# UNG_8088_EVB_LAN9252-SPI_Copper.net
KiCad netlist of a schematic drawn in Altium Designer
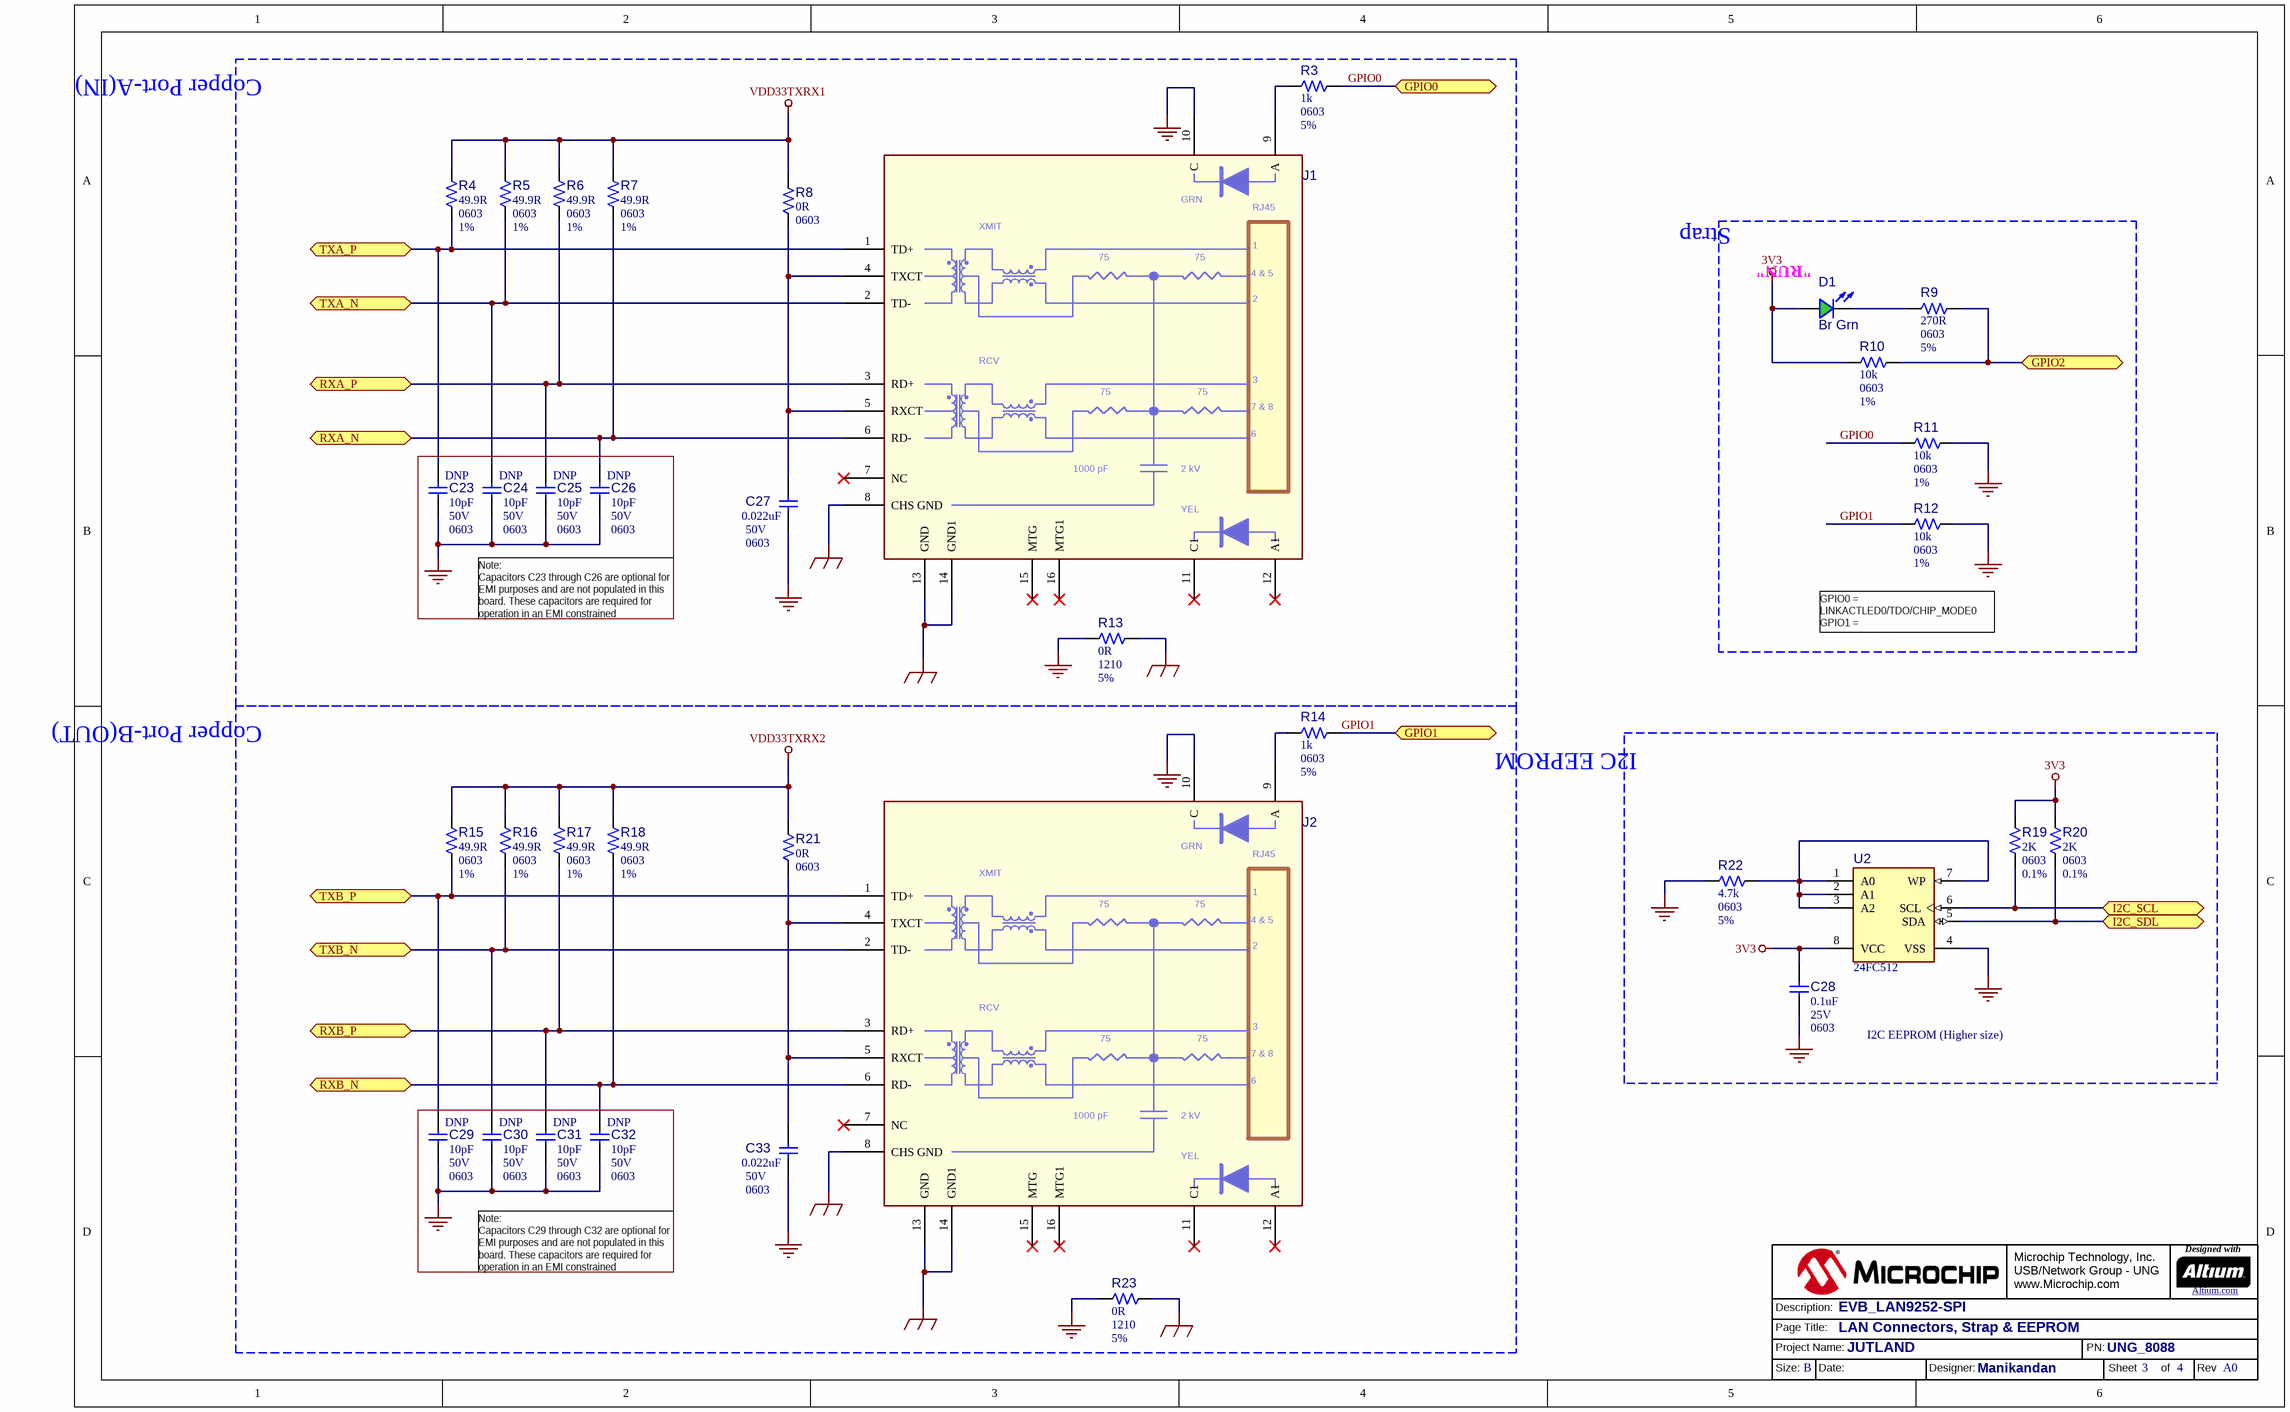
[diagram p0: UNG_8088_EVB_LAN9252-SPI_Copper.SchDoc]

(export (version "E")
  (design (tool "Eeschema 10.0.6"))
  (components
    (comp (ref "C23")
      (value "10pF")
      (footprint "CAP_C_0603")
      (description "Capacitor")
      (fields
        (field (name "VOLTAGE") "50V")
        (field (name "PACKAGE") "0603")
        (field (name "TOLERANCE") "5%")
        (field (name "POPULATED") "DNP")
        (field (name "Comment") "Capacitor NP")
      )
      (libsource (lib "MCHP-CDB-Offline") (part "Capacitor NP"))
    )
    (comp (ref "C24")
      (value "10pF")
      (footprint "CAP_C_0603")
      (description "Capacitor")
      (fields
        (field (name "VOLTAGE") "50V")
        (field (name "PACKAGE") "0603")
        (field (name "TOLERANCE") "5%")
        (field (name "POPULATED") "DNP")
        (field (name "Comment") "Capacitor NP")
      )
      (libsource (lib "MCHP-CDB-Offline") (part "Capacitor NP"))
    )
    (comp (ref "C25")
      (value "10pF")
      (footprint "CAP_C_0603")
      (description "Capacitor")
      (fields
        (field (name "VOLTAGE") "50V")
        (field (name "PACKAGE") "0603")
        (field (name "TOLERANCE") "5%")
        (field (name "POPULATED") "DNP")
        (field (name "Comment") "Capacitor NP")
      )
      (libsource (lib "MCHP-CDB-Offline") (part "Capacitor NP"))
    )
    (comp (ref "C26")
      (value "10pF")
      (footprint "CAP_C_0603")
      (description "Capacitor")
      (fields
        (field (name "VOLTAGE") "50V")
        (field (name "PACKAGE") "0603")
        (field (name "TOLERANCE") "5%")
        (field (name "POPULATED") "DNP")
        (field (name "Comment") "Capacitor NP")
      )
      (libsource (lib "MCHP-CDB-Offline") (part "Capacitor NP"))
    )
    (comp (ref "C27")
      (value "0.022uF")
      (footprint "CAP_C_0603")
      (description "Capacitor")
      (fields
        (field (name "VOLTAGE") "50V")
        (field (name "PACKAGE") "0603")
        (field (name "TOLERANCE") "5%")
        (field (name "Comment") "Capacitor NP")
      )
      (libsource (lib "MCHP-CDB-Offline") (part "Capacitor NP"))
    )
    (comp (ref "C28")
      (value "0.1uF")
      (footprint "CAP_C_0603")
      (description "Capacitor")
      (fields
        (field (name "VOLTAGE") "25V")
        (field (name "PACKAGE") "0603")
        (field (name "TOLERANCE") "20%")
        (field (name "Comment") "Capacitor NP")
      )
      (libsource (lib "MCHP-CDB-Offline") (part "Capacitor NP"))
    )
    (comp (ref "C29")
      (value "10pF")
      (footprint "CAP_C_0603")
      (description "Capacitor")
      (fields
        (field (name "VOLTAGE") "50V")
        (field (name "PACKAGE") "0603")
        (field (name "TOLERANCE") "5%")
        (field (name "POPULATED") "DNP")
        (field (name "Comment") "Capacitor NP")
      )
      (libsource (lib "MCHP-CDB-Offline") (part "Capacitor NP"))
    )
    (comp (ref "C30")
      (value "10pF")
      (footprint "CAP_C_0603")
      (description "Capacitor")
      (fields
        (field (name "VOLTAGE") "50V")
        (field (name "PACKAGE") "0603")
        (field (name "TOLERANCE") "5%")
        (field (name "POPULATED") "DNP")
        (field (name "Comment") "Capacitor NP")
      )
      (libsource (lib "MCHP-CDB-Offline") (part "Capacitor NP"))
    )
    (comp (ref "C31")
      (value "10pF")
      (footprint "CAP_C_0603")
      (description "Capacitor")
      (fields
        (field (name "VOLTAGE") "50V")
        (field (name "PACKAGE") "0603")
        (field (name "TOLERANCE") "5%")
        (field (name "POPULATED") "DNP")
        (field (name "Comment") "Capacitor NP")
      )
      (libsource (lib "MCHP-CDB-Offline") (part "Capacitor NP"))
    )
    (comp (ref "C32")
      (value "10pF")
      (footprint "CAP_C_0603")
      (description "Capacitor")
      (fields
        (field (name "VOLTAGE") "50V")
        (field (name "PACKAGE") "0603")
        (field (name "TOLERANCE") "5%")
        (field (name "POPULATED") "DNP")
        (field (name "Comment") "Capacitor NP")
      )
      (libsource (lib "MCHP-CDB-Offline") (part "Capacitor NP"))
    )
    (comp (ref "C33")
      (value "0.022uF")
      (footprint "CAP_C_0603")
      (description "Capacitor")
      (fields
        (field (name "VOLTAGE") "50V")
        (field (name "PACKAGE") "0603")
        (field (name "TOLERANCE") "5%")
        (field (name "Comment") "Capacitor NP")
      )
      (libsource (lib "MCHP-CDB-Offline") (part "Capacitor NP"))
    )
    (comp (ref "D1")
      (value "Br Grn")
      (footprint "LED_0603_GREEN")
      (description "LED, Bright Green, 0603")
      (fields (field (name "OWNER") "Jennifer Hancock"))
      (libsource (lib "UNG_DIODES") (part "LED, Bright Green, 0603"))
    )
    (comp (ref "J1")
      (value "CONN RJ45 J0011D01BNL")
      (footprint "RJ45_J0011D01BNL")
      (description "CONN RJ45 TH PULSE J0011D01BNL")
      (fields (field (name "OWNER") "Manikandan"))
      (libsource (lib "UNG_CONNECTORS") (part "CONN RJ45 TH PULSE J0011D01BNL"))
    )
    (comp (ref "J2")
      (value "CONN RJ45 J0011D01BNL")
      (footprint "RJ45_J0011D01BNL")
      (description "CONN RJ45 TH PULSE J0011D01BNL")
      (fields (field (name "OWNER") "Manikandan"))
      (libsource (lib "UNG_CONNECTORS") (part "CONN RJ45 TH PULSE J0011D01BNL"))
    )
    (comp (ref "R3")
      (value "1k")
      (footprint "RES_C_0603")
      (description "Resistor")
      (fields
        (field (name "PACKAGE") "0603")
        (field (name "TOLERANCE") "5%")
        (field (name "VOLTAGE") "75V")
        (field (name "POWER") "1/10W")
        (field (name "OWNER") "Bogdan P (M91398)")
      )
      (libsource (lib "MCHP-CDB-Offline") (part "Resistor"))
    )
    (comp (ref "R4")
      (value "49.9R")
      (footprint "RES_C_0603")
      (description "Resistor")
      (fields
        (field (name "PACKAGE") "0603")
        (field (name "TOLERANCE") "1%")
        (field (name "VOLTAGE") "75V")
        (field (name "POWER") "1/10W")
        (field (name "OWNER") "Adrian T (M91397)")
      )
      (libsource (lib "MCHP-CDB-Offline") (part "Resistor"))
    )
    (comp (ref "R5")
      (value "49.9R")
      (footprint "RES_C_0603")
      (description "Resistor")
      (fields
        (field (name "PACKAGE") "0603")
        (field (name "TOLERANCE") "1%")
        (field (name "VOLTAGE") "75V")
        (field (name "POWER") "1/10W")
        (field (name "OWNER") "Adrian T (M91397)")
      )
      (libsource (lib "MCHP-CDB-Offline") (part "Resistor"))
    )
    (comp (ref "R6")
      (value "49.9R")
      (footprint "RES_C_0603")
      (description "Resistor")
      (fields
        (field (name "PACKAGE") "0603")
        (field (name "TOLERANCE") "1%")
        (field (name "VOLTAGE") "75V")
        (field (name "POWER") "1/10W")
        (field (name "OWNER") "Adrian T (M91397)")
      )
      (libsource (lib "MCHP-CDB-Offline") (part "Resistor"))
    )
    (comp (ref "R7")
      (value "49.9R")
      (footprint "RES_C_0603")
      (description "Resistor")
      (fields
        (field (name "PACKAGE") "0603")
        (field (name "TOLERANCE") "1%")
        (field (name "VOLTAGE") "75V")
        (field (name "POWER") "1/10W")
        (field (name "OWNER") "Adrian T (M91397)")
      )
      (libsource (lib "MCHP-CDB-Offline") (part "Resistor"))
    )
    (comp (ref "R8")
      (value "0R")
      (footprint "RES_C_0603")
      (description "Resistor")
      (fields (field (name "PACKAGE") "0603") (field (name "POWER") "1/10W"))
      (libsource (lib "MCHP-CDB-Offline") (part "Resistor"))
    )
    (comp (ref "R9")
      (value "270R")
      (footprint "RES_C_0603")
      (description "Resistor")
      (fields
        (field (name "PACKAGE") "0603")
        (field (name "TOLERANCE") "5%")
        (field (name "VOLTAGE") "75V")
        (field (name "POWER") "1/10W")
        (field (name "OWNER") "Bogdan P (M91398)")
      )
      (libsource (lib "MCHP-CDB") (part "Resistor"))
    )
    (comp (ref "R10")
      (value "10k")
      (footprint "RES_C_0603")
      (description "Resistor")
      (fields
        (field (name "PACKAGE") "0603")
        (field (name "TOLERANCE") "1%")
        (field (name "VOLTAGE") "100V")
        (field (name "POWER") "1/16W")
        (field (name "OWNER") "Jairuz Agang-ang")
      )
      (libsource (lib "MCHP-CDB-Offline") (part "Resistor"))
    )
    (comp (ref "R11")
      (value "10k")
      (footprint "RES_C_0603")
      (description "Resistor")
      (fields
        (field (name "PACKAGE") "0603")
        (field (name "TOLERANCE") "1%")
        (field (name "VOLTAGE") "100V")
        (field (name "POWER") "1/16W")
        (field (name "OWNER") "Jairuz Agang-ang")
      )
      (libsource (lib "MCHP-CDB-Offline") (part "Resistor"))
    )
    (comp (ref "R12")
      (value "10k")
      (footprint "RES_C_0603")
      (description "Resistor")
      (fields
        (field (name "PACKAGE") "0603")
        (field (name "TOLERANCE") "1%")
        (field (name "VOLTAGE") "100V")
        (field (name "POWER") "1/16W")
        (field (name "OWNER") "Jairuz Agang-ang")
      )
      (libsource (lib "MCHP-CDB-Offline") (part "Resistor"))
    )
    (comp (ref "R13")
      (value "0R")
      (footprint "RES_C_1210")
      (description "Resistor")
      (fields (field (name "PACKAGE") "1210") (field (name "TOLERANCE") "5%") (field (name "POWER") "1/3W"))
      (libsource (lib "MCHP-CDB-Offline") (part "Resistor"))
    )
    (comp (ref "R14")
      (value "1k")
      (footprint "RES_C_0603")
      (description "Resistor")
      (fields
        (field (name "PACKAGE") "0603")
        (field (name "TOLERANCE") "5%")
        (field (name "VOLTAGE") "75V")
        (field (name "POWER") "1/10W")
        (field (name "OWNER") "Bogdan P (M91398)")
      )
      (libsource (lib "MCHP-CDB-Offline") (part "Resistor"))
    )
    (comp (ref "R15")
      (value "49.9R")
      (footprint "RES_C_0603")
      (description "Resistor")
      (fields
        (field (name "PACKAGE") "0603")
        (field (name "TOLERANCE") "1%")
        (field (name "VOLTAGE") "75V")
        (field (name "POWER") "1/10W")
        (field (name "OWNER") "Adrian T (M91397)")
      )
      (libsource (lib "MCHP-CDB-Offline") (part "Resistor"))
    )
    (comp (ref "R16")
      (value "49.9R")
      (footprint "RES_C_0603")
      (description "Resistor")
      (fields
        (field (name "PACKAGE") "0603")
        (field (name "TOLERANCE") "1%")
        (field (name "VOLTAGE") "75V")
        (field (name "POWER") "1/10W")
        (field (name "OWNER") "Adrian T (M91397)")
      )
      (libsource (lib "MCHP-CDB-Offline") (part "Resistor"))
    )
    (comp (ref "R17")
      (value "49.9R")
      (footprint "RES_C_0603")
      (description "Resistor")
      (fields
        (field (name "PACKAGE") "0603")
        (field (name "TOLERANCE") "1%")
        (field (name "VOLTAGE") "75V")
        (field (name "POWER") "1/10W")
        (field (name "OWNER") "Adrian T (M91397)")
      )
      (libsource (lib "MCHP-CDB-Offline") (part "Resistor"))
    )
    (comp (ref "R18")
      (value "49.9R")
      (footprint "RES_C_0603")
      (description "Resistor")
      (fields
        (field (name "PACKAGE") "0603")
        (field (name "TOLERANCE") "1%")
        (field (name "VOLTAGE") "75V")
        (field (name "POWER") "1/10W")
        (field (name "OWNER") "Adrian T (M91397)")
      )
      (libsource (lib "MCHP-CDB-Offline") (part "Resistor"))
    )
    (comp (ref "R19")
      (value "2K")
      (footprint "RES_C_0603")
      (description "Resistor")
      (fields
        (field (name "PACKAGE") "0603")
        (field (name "TOLERANCE") "0.1%")
        (field (name "POWER") "0.1W, 1/10W")
        (field (name "OWNER") "Jose Garcia")
      )
      (libsource (lib "MCHP-CDB") (part "Resistor"))
    )
    (comp (ref "R20")
      (value "2K")
      (footprint "RES_C_0603")
      (description "Resistor")
      (fields
        (field (name "PACKAGE") "0603")
        (field (name "TOLERANCE") "0.1%")
        (field (name "POWER") "0.1W, 1/10W")
        (field (name "OWNER") "Jose Garcia")
      )
      (libsource (lib "MCHP-CDB") (part "Resistor"))
    )
    (comp (ref "R21")
      (value "0R")
      (footprint "RES_C_0603")
      (description "Resistor")
      (fields (field (name "PACKAGE") "0603") (field (name "POWER") "1/10W"))
      (libsource (lib "MCHP-CDB-Offline") (part "Resistor"))
    )
    (comp (ref "R22")
      (value "4.7k")
      (footprint "RES_C_0603")
      (description "Resistor")
      (fields
        (field (name "PACKAGE") "0603")
        (field (name "TOLERANCE") "5%")
        (field (name "VOLTAGE") "75V")
        (field (name "POWER") "1/10W")
        (field (name "OWNER") "Bogdan P (M91398)")
      )
      (libsource (lib "MCHP-CDB") (part "Resistor"))
    )
    (comp (ref "R23")
      (value "0R")
      (footprint "RES_C_1210")
      (description "Resistor")
      (fields (field (name "PACKAGE") "1210") (field (name "TOLERANCE") "5%") (field (name "POWER") "1/3W"))
      (libsource (lib "MCHP-CDB-Offline") (part "Resistor"))
    )
    (comp (ref "U2")
      (value "24FC512")
      (footprint "SOIC-8")
      (description "EEPROM I2C")
      (libsource (lib "UNG_IC") (part "24FC512"))
    )
  )
  (nets
    (net (code "1") (name "/GPIO0") (class "Default")
      (node (ref "R11") (pin "2") (pinfunction "2_2") (pintype "passive"))
      (node (ref "R3") (pin "2") (pinfunction "2_2") (pintype "passive"))
    )
    (net (code "2") (name "/GPIO1") (class "Default")
      (node (ref "R12") (pin "2") (pinfunction "2_2") (pintype "passive"))
      (node (ref "R14") (pin "2") (pinfunction "2_2") (pintype "passive"))
    )
    (net (code "3") (name "/GPIO2") (class "Default")
      (node (ref "R10") (pin "1") (pinfunction "1_1") (pintype "passive"))
      (node (ref "R9") (pin "1") (pinfunction "1_1") (pintype "passive"))
    )
    (net (code "4") (name "/I2C_SCL") (class "Default")
      (node (ref "R19") (pin "1") (pinfunction "1_1") (pintype "passive"))
      (node (ref "U2") (pin "6") (pinfunction "SCL_6") (pintype "input"))
    )
    (net (code "5") (name "/I2C_SDL") (class "Default")
      (node (ref "R20") (pin "1") (pinfunction "1_1") (pintype "passive"))
      (node (ref "U2") (pin "5") (pinfunction "SDA_5") (pintype "bidirectional"))
    )
    (net (code "6") (name "/RXA_N") (class "Default")
      (node (ref "C26") (pin "2") (pinfunction "2_2") (pintype "passive"))
      (node (ref "J1") (pin "6") (pinfunction "RD-_6") (pintype "passive"))
      (node (ref "R7") (pin "1") (pinfunction "1_1") (pintype "passive"))
    )
    (net (code "7") (name "/RXA_P") (class "Default")
      (node (ref "C25") (pin "2") (pinfunction "2_2") (pintype "passive"))
      (node (ref "J1") (pin "3") (pinfunction "RD+_3") (pintype "passive"))
      (node (ref "R6") (pin "1") (pinfunction "1_1") (pintype "passive"))
    )
    (net (code "8") (name "/RXB_N") (class "Default")
      (node (ref "C32") (pin "2") (pinfunction "2_2") (pintype "passive"))
      (node (ref "J2") (pin "6") (pinfunction "RD-_6") (pintype "passive"))
      (node (ref "R18") (pin "1") (pinfunction "1_1") (pintype "passive"))
    )
    (net (code "9") (name "/RXB_P") (class "Default")
      (node (ref "C31") (pin "2") (pinfunction "2_2") (pintype "passive"))
      (node (ref "J2") (pin "3") (pinfunction "RD+_3") (pintype "passive"))
      (node (ref "R17") (pin "1") (pinfunction "1_1") (pintype "passive"))
    )
    (net (code "10") (name "/TXA_N") (class "Default")
      (node (ref "C24") (pin "2") (pinfunction "2_2") (pintype "passive"))
      (node (ref "J1") (pin "2") (pinfunction "TD-_2") (pintype "passive"))
      (node (ref "R5") (pin "1") (pinfunction "1_1") (pintype "passive"))
    )
    (net (code "11") (name "/TXA_P") (class "Default")
      (node (ref "C23") (pin "2") (pinfunction "2_2") (pintype "passive"))
      (node (ref "J1") (pin "1") (pinfunction "TD+_1") (pintype "passive"))
      (node (ref "R4") (pin "1") (pinfunction "1_1") (pintype "passive"))
    )
    (net (code "12") (name "/TXB_N") (class "Default")
      (node (ref "C30") (pin "2") (pinfunction "2_2") (pintype "passive"))
      (node (ref "J2") (pin "2") (pinfunction "TD-_2") (pintype "passive"))
      (node (ref "R16") (pin "1") (pinfunction "1_1") (pintype "passive"))
    )
    (net (code "13") (name "/TXB_P") (class "Default")
      (node (ref "C29") (pin "2") (pinfunction "2_2") (pintype "passive"))
      (node (ref "J2") (pin "1") (pinfunction "TD+_1") (pintype "passive"))
      (node (ref "R15") (pin "1") (pinfunction "1_1") (pintype "passive"))
    )
    (net (code "14") (name "3V3") (class "Default")
      (node (ref "C28") (pin "2") (pinfunction "2_2") (pintype "passive"))
      (node (ref "D1") (pin "1") (pinfunction "A_1") (pintype "passive"))
      (node (ref "R10") (pin "2") (pinfunction "2_2") (pintype "passive"))
      (node (ref "R19") (pin "2") (pinfunction "2_2") (pintype "passive"))
      (node (ref "R20") (pin "2") (pinfunction "2_2") (pintype "passive"))
      (node (ref "U2") (pin "8") (pinfunction "VCC_8") (pintype "power_in"))
    )
    (net (code "15") (name "Earth1") (class "Default")
      (node (ref "J1") (pin "13") (pinfunction "GND_13") (pintype "passive"))
      (node (ref "J1") (pin "14") (pinfunction "GND1_14") (pintype "passive"))
      (node (ref "J1") (pin "8") (pinfunction "CHS_GND_8") (pintype "passive"))
      (node (ref "R13") (pin "2") (pinfunction "2_2") (pintype "passive"))
    )
    (net (code "16") (name "Earth2") (class "Default")
      (node (ref "J2") (pin "13") (pinfunction "GND_13") (pintype "passive"))
      (node (ref "J2") (pin "14") (pinfunction "GND1_14") (pintype "passive"))
      (node (ref "J2") (pin "8") (pinfunction "CHS_GND_8") (pintype "passive"))
      (node (ref "R23") (pin "2") (pinfunction "2_2") (pintype "passive"))
    )
    (net (code "17") (name "GND") (class "Default")
      (node (ref "C23") (pin "1") (pinfunction "1_1") (pintype "passive"))
      (node (ref "C24") (pin "1") (pinfunction "1_1") (pintype "passive"))
      (node (ref "C25") (pin "1") (pinfunction "1_1") (pintype "passive"))
      (node (ref "C26") (pin "1") (pinfunction "1_1") (pintype "passive"))
      (node (ref "C27") (pin "1") (pinfunction "1_1") (pintype "passive"))
      (node (ref "C28") (pin "1") (pinfunction "1_1") (pintype "passive"))
      (node (ref "C29") (pin "1") (pinfunction "1_1") (pintype "passive"))
      (node (ref "C30") (pin "1") (pinfunction "1_1") (pintype "passive"))
      (node (ref "C31") (pin "1") (pinfunction "1_1") (pintype "passive"))
      (node (ref "C32") (pin "1") (pinfunction "1_1") (pintype "passive"))
      (node (ref "C33") (pin "1") (pinfunction "1_1") (pintype "passive"))
      (node (ref "J1") (pin "10") (pinfunction "C_10") (pintype "passive"))
      (node (ref "J2") (pin "10") (pinfunction "C_10") (pintype "passive"))
      (node (ref "R11") (pin "1") (pinfunction "1_1") (pintype "passive"))
      (node (ref "R12") (pin "1") (pinfunction "1_1") (pintype "passive"))
      (node (ref "R13") (pin "1") (pinfunction "1_1") (pintype "passive"))
      (node (ref "R22") (pin "1") (pinfunction "1_1") (pintype "passive"))
      (node (ref "R23") (pin "1") (pinfunction "1_1") (pintype "passive"))
      (node (ref "U2") (pin "4") (pinfunction "VSS_4") (pintype "power_in"))
    )
    (net (code "18") (name "Net-(D1-K)") (class "Default")
      (node (ref "D1") (pin "2") (pinfunction "K_2") (pintype "passive"))
      (node (ref "R9") (pin "2") (pinfunction "2_2") (pintype "passive"))
    )
    (net (code "19") (name "Net-(J1-A)") (class "Default")
      (node (ref "J1") (pin "9") (pinfunction "A_9") (pintype "passive"))
      (node (ref "R3") (pin "1") (pinfunction "1_1") (pintype "passive"))
    )
    (net (code "20") (name "Net-(J1-RXCT)") (class "Default")
      (node (ref "C27") (pin "2") (pinfunction "2_2") (pintype "passive"))
      (node (ref "J1") (pin "4") (pinfunction "TXCT_4") (pintype "passive"))
      (node (ref "J1") (pin "5") (pinfunction "RXCT_5") (pintype "passive"))
      (node (ref "R8") (pin "1") (pinfunction "1_1") (pintype "passive"))
    )
    (net (code "21") (name "Net-(J2-A)") (class "Default")
      (node (ref "J2") (pin "9") (pinfunction "A_9") (pintype "passive"))
      (node (ref "R14") (pin "1") (pinfunction "1_1") (pintype "passive"))
    )
    (net (code "22") (name "Net-(J2-RXCT)") (class "Default")
      (node (ref "C33") (pin "2") (pinfunction "2_2") (pintype "passive"))
      (node (ref "J2") (pin "4") (pinfunction "TXCT_4") (pintype "passive"))
      (node (ref "J2") (pin "5") (pinfunction "RXCT_5") (pintype "passive"))
      (node (ref "R21") (pin "1") (pinfunction "1_1") (pintype "passive"))
    )
    (net (code "23") (name "Net-(U2-A0)") (class "Default")
      (node (ref "R22") (pin "2") (pinfunction "2_2") (pintype "passive"))
      (node (ref "U2") (pin "1") (pinfunction "A0_1") (pintype "passive"))
      (node (ref "U2") (pin "2") (pinfunction "A1_2") (pintype "passive"))
      (node (ref "U2") (pin "3") (pinfunction "A2_3") (pintype "passive"))
      (node (ref "U2") (pin "7") (pinfunction "WP_7") (pintype "input"))
    )
    (net (code "24") (name "VDD33TXRX1") (class "Default")
      (node (ref "R4") (pin "2") (pinfunction "2_2") (pintype "passive"))
      (node (ref "R5") (pin "2") (pinfunction "2_2") (pintype "passive"))
      (node (ref "R6") (pin "2") (pinfunction "2_2") (pintype "passive"))
      (node (ref "R7") (pin "2") (pinfunction "2_2") (pintype "passive"))
      (node (ref "R8") (pin "2") (pinfunction "2_2") (pintype "passive"))
    )
    (net (code "25") (name "VDD33TXRX2") (class "Default")
      (node (ref "R15") (pin "2") (pinfunction "2_2") (pintype "passive"))
      (node (ref "R16") (pin "2") (pinfunction "2_2") (pintype "passive"))
      (node (ref "R17") (pin "2") (pinfunction "2_2") (pintype "passive"))
      (node (ref "R18") (pin "2") (pinfunction "2_2") (pintype "passive"))
      (node (ref "R21") (pin "2") (pinfunction "2_2") (pintype "passive"))
    )
    (net (code "26") (name "unconnected-(J1-A1-Pad12)") (class "Default")
      (node (ref "J1") (pin "12") (pinfunction "A1_12") (pintype "passive+no_connect"))
    )
    (net (code "27") (name "unconnected-(J1-C1-Pad11)") (class "Default")
      (node (ref "J1") (pin "11") (pinfunction "C1_11") (pintype "passive+no_connect"))
    )
    (net (code "28") (name "unconnected-(J1-MTG-Pad15)") (class "Default")
      (node (ref "J1") (pin "15") (pinfunction "MTG_15") (pintype "passive+no_connect"))
    )
    (net (code "29") (name "unconnected-(J1-MTG1-Pad16)") (class "Default")
      (node (ref "J1") (pin "16") (pinfunction "MTG1_16") (pintype "passive+no_connect"))
    )
    (net (code "30") (name "unconnected-(J1-NC-Pad7)") (class "Default")
      (node (ref "J1") (pin "7") (pinfunction "NC_7") (pintype "passive+no_connect"))
    )
    (net (code "31") (name "unconnected-(J2-A1-Pad12)") (class "Default")
      (node (ref "J2") (pin "12") (pinfunction "A1_12") (pintype "passive+no_connect"))
    )
    (net (code "32") (name "unconnected-(J2-C1-Pad11)") (class "Default")
      (node (ref "J2") (pin "11") (pinfunction "C1_11") (pintype "passive+no_connect"))
    )
    (net (code "33") (name "unconnected-(J2-MTG-Pad15)") (class "Default")
      (node (ref "J2") (pin "15") (pinfunction "MTG_15") (pintype "passive+no_connect"))
    )
    (net (code "34") (name "unconnected-(J2-MTG1-Pad16)") (class "Default")
      (node (ref "J2") (pin "16") (pinfunction "MTG1_16") (pintype "passive+no_connect"))
    )
    (net (code "35") (name "unconnected-(J2-NC-Pad7)") (class "Default")
      (node (ref "J2") (pin "7") (pinfunction "NC_7") (pintype "passive+no_connect"))
    )
  )
)
